# cpu-18f4455.net
KiCad netlist of a schematic drawn in EAGLE
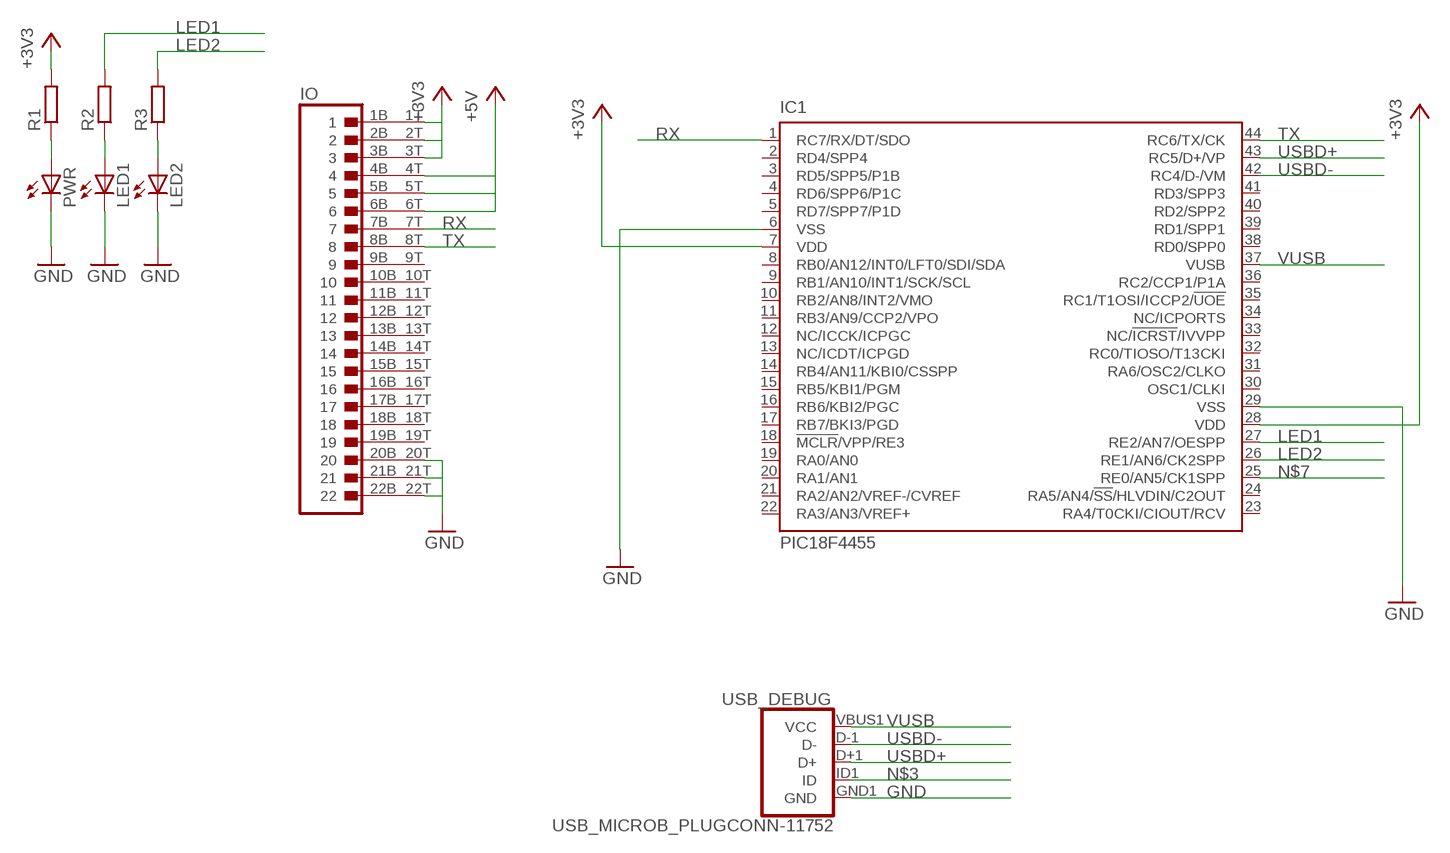
[diagram p0: schematic, sheet 1]

(export (version "E")
  (design (tool "Eeschema 10.0.6"))
  (components
    (comp (ref "IC1")
      (value "PIC18F4455")
      (footprint "eagle-import:TQFP44")
      (fields (field (name "MF") "MICROCHIP") (field (name "MPN") "PIC18F4455-I/PT"))
      (libsource (lib "eagle-import") (part "PIC18F4_TQFP455"))
    )
    (comp (ref "IO")
      (value "SIMBRD22")
      (footprint "eagle-import:SIMBRD22")
      (libsource (lib "eagle-import") (part "SIMBRD22"))
    )
    (comp (ref "LED1")
      (value "LED1206")
      (footprint "eagle-import:LED-1206")
      (libsource (lib "eagle-import") (part "LED1206"))
    )
    (comp (ref "LED2")
      (value "LED1206")
      (footprint "eagle-import:LED-1206")
      (libsource (lib "eagle-import") (part "LED1206"))
    )
    (comp (ref "PWR")
      (value "LED1206")
      (footprint "eagle-import:LED-1206")
      (libsource (lib "eagle-import") (part "LED1206"))
    )
    (comp (ref "R1")
      (value "R-EU_R0805")
      (footprint "eagle-import:R0805")
      (libsource (lib "eagle-import") (part "R-EU_R0805"))
    )
    (comp (ref "R2")
      (value "R-EU_R0805")
      (footprint "eagle-import:R0805")
      (libsource (lib "eagle-import") (part "R-EU_R0805"))
    )
    (comp (ref "R3")
      (value "R-EU_R0805")
      (footprint "eagle-import:R0805")
      (libsource (lib "eagle-import") (part "R-EU_R0805"))
    )
    (comp (ref "USB_DEBUG")
      (value "USB_MICROB_PLUGCONN-11752")
      (footprint "eagle-import:USB-B-MICRO-SMD_V03")
      (libsource (lib "eagle-import") (part "USB_MICROB_PLUGCONN-11752"))
    )
  )
  (nets
    (net (code "1") (name "+3V3") (class "Default")
      (node (ref "IC1") (pin "28") (pinfunction "VDD_28") (pintype "power_in"))
      (node (ref "IC1") (pin "7") (pinfunction "VDD_7") (pintype "power_in"))
      (node (ref "IO") (pin "1T") (pinfunction "A1_1T") (pintype "passive"))
      (node (ref "IO") (pin "2T") (pinfunction "A2_2T") (pintype "passive"))
      (node (ref "IO") (pin "3T") (pinfunction "A3_3T") (pintype "passive"))
      (node (ref "R1") (pin "2") (pinfunction "2_2") (pintype "passive"))
    )
    (net (code "2") (name "+5V") (class "Default")
      (node (ref "IO") (pin "4T") (pinfunction "A4_4T") (pintype "passive"))
      (node (ref "IO") (pin "5T") (pinfunction "A5_5T") (pintype "passive"))
      (node (ref "IO") (pin "6T") (pinfunction "A6_6T") (pintype "passive"))
    )
    (net (code "3") (name "/LED1") (class "Default")
      (node (ref "IC1") (pin "27") (pinfunction "RE2/AN7/OESPP_27") (pintype "bidirectional"))
      (node (ref "R2") (pin "2") (pinfunction "2_2") (pintype "passive"))
    )
    (net (code "4") (name "/LED2") (class "Default")
      (node (ref "IC1") (pin "26") (pinfunction "RE1/AN6/CK2SPP_26") (pintype "bidirectional"))
      (node (ref "R3") (pin "2") (pinfunction "2_2") (pintype "passive"))
    )
    (net (code "5") (name "/N$3") (class "Default")
      (node (ref "USB_DEBUG") (pin "ID1") (pinfunction "ID_ID1") (pintype "bidirectional"))
    )
    (net (code "6") (name "/N$7") (class "Default")
      (node (ref "IC1") (pin "25") (pinfunction "RE0/AN5/CK1SPP_25") (pintype "bidirectional"))
    )
    (net (code "7") (name "/RX") (class "Default")
      (node (ref "IC1") (pin "1") (pinfunction "RC7/RX/DT/SDO_1") (pintype "bidirectional"))
      (node (ref "IO") (pin "7T") (pinfunction "A7_7T") (pintype "passive"))
    )
    (net (code "8") (name "/TX") (class "Default")
      (node (ref "IC1") (pin "44") (pinfunction "RC6/TX/CK_44") (pintype "bidirectional"))
      (node (ref "IO") (pin "8T") (pinfunction "A8_8T") (pintype "passive"))
    )
    (net (code "9") (name "/USBD+") (class "Default")
      (node (ref "IC1") (pin "43") (pinfunction "RC5/D+/VP_43") (pintype "bidirectional"))
      (node (ref "USB_DEBUG") (pin "D+1") (pinfunction "D+_D+1") (pintype "bidirectional"))
    )
    (net (code "10") (name "/USBD-") (class "Default")
      (node (ref "IC1") (pin "42") (pinfunction "RC4/D-/VM_42") (pintype "bidirectional"))
      (node (ref "USB_DEBUG") (pin "D-1") (pinfunction "D-_D-1") (pintype "bidirectional"))
    )
    (net (code "11") (name "/VUSB") (class "Default")
      (node (ref "IC1") (pin "37") (pinfunction "VUSB_37") (pintype "bidirectional"))
      (node (ref "USB_DEBUG") (pin "VBUS1") (pinfunction "VCC_VBUS1") (pintype "bidirectional"))
    )
    (net (code "12") (name "GND") (class "Default")
      (node (ref "IC1") (pin "29") (pinfunction "VSS_29") (pintype "power_in"))
      (node (ref "IC1") (pin "6") (pinfunction "VSS_6") (pintype "power_in"))
      (node (ref "IO") (pin "20T") (pinfunction "A20_20T") (pintype "passive"))
      (node (ref "IO") (pin "21T") (pinfunction "A21_21T") (pintype "passive"))
      (node (ref "IO") (pin "22T") (pinfunction "A22_22T") (pintype "passive"))
      (node (ref "LED1") (pin "C") (pinfunction "C_C") (pintype "passive"))
      (node (ref "LED2") (pin "C") (pinfunction "C_C") (pintype "passive"))
      (node (ref "PWR") (pin "C") (pinfunction "C_C") (pintype "passive"))
      (node (ref "USB_DEBUG") (pin "GND1") (pinfunction "GND_GND1") (pintype "bidirectional"))
    )
    (net (code "13") (name "Net-(LED1-PadA)") (class "Default")
      (node (ref "LED1") (pin "A") (pinfunction "A_A") (pintype "passive"))
      (node (ref "R2") (pin "1") (pinfunction "1_1") (pintype "passive"))
    )
    (net (code "14") (name "Net-(LED2-PadA)") (class "Default")
      (node (ref "LED2") (pin "A") (pinfunction "A_A") (pintype "passive"))
      (node (ref "R3") (pin "1") (pinfunction "1_1") (pintype "passive"))
    )
    (net (code "15") (name "Net-(PWR-PadA)") (class "Default")
      (node (ref "PWR") (pin "A") (pinfunction "A_A") (pintype "passive"))
      (node (ref "R1") (pin "1") (pinfunction "1_1") (pintype "passive"))
    )
    (net (code "16") (name "unconnected-(IC1-NC{slash}ICCK{slash}ICPGC-Pad12)") (class "Default")
      (node (ref "IC1") (pin "12") (pinfunction "NC/ICCK/ICPGC_12") (pintype "bidirectional"))
    )
    (net (code "17") (name "unconnected-(IC1-NC{slash}ICDT{slash}ICPGD-Pad13)") (class "Default")
      (node (ref "IC1") (pin "13") (pinfunction "NC/ICDT/ICPGD_13") (pintype "bidirectional"))
    )
    (net (code "18") (name "unconnected-(IC1-NC{slash}ICPORTS-Pad34)") (class "Default")
      (node (ref "IC1") (pin "34") (pinfunction "NC/ICPORTS_34") (pintype "input"))
    )
    (net (code "19") (name "unconnected-(IC1-NC{slash}~{ICRST}{slash}IVVPP-Pad33)") (class "Default")
      (node (ref "IC1") (pin "33") (pinfunction "NC/~{ICRST}/IVVPP_33") (pintype "input"))
    )
    (net (code "20") (name "unconnected-(IC1-OSC1{slash}CLKI-Pad30)") (class "Default")
      (node (ref "IC1") (pin "30") (pinfunction "OSC1/CLKI_30") (pintype "input"))
    )
    (net (code "21") (name "unconnected-(IC1-RA0{slash}AN0-Pad19)") (class "Default")
      (node (ref "IC1") (pin "19") (pinfunction "RA0/AN0_19") (pintype "bidirectional"))
    )
    (net (code "22") (name "unconnected-(IC1-RA1{slash}AN1-Pad20)") (class "Default")
      (node (ref "IC1") (pin "20") (pinfunction "RA1/AN1_20") (pintype "bidirectional"))
    )
    (net (code "23") (name "unconnected-(IC1-RA2{slash}AN2{slash}VREF-{slash}CVREF-Pad21)") (class "Default")
      (node (ref "IC1") (pin "21") (pinfunction "RA2/AN2/VREF-/CVREF_21") (pintype "bidirectional"))
    )
    (net (code "24") (name "unconnected-(IC1-RA3{slash}AN3{slash}VREF+-Pad22)") (class "Default")
      (node (ref "IC1") (pin "22") (pinfunction "RA3/AN3/VREF+_22") (pintype "bidirectional"))
    )
    (net (code "25") (name "unconnected-(IC1-RA4{slash}T0CKI{slash}CIOUT{slash}RCV-Pad23)") (class "Default")
      (node (ref "IC1") (pin "23") (pinfunction "RA4/T0CKI/CIOUT/RCV_23") (pintype "bidirectional"))
    )
    (net (code "26") (name "unconnected-(IC1-RA5{slash}AN4{slash}~{SS}{slash}HLVDIN{slash}C2OUT-Pad24)") (class "Default")
      (node (ref "IC1") (pin "24") (pinfunction "RA5/AN4/~{SS}/HLVDIN/C2OUT_24") (pintype "bidirectional"))
    )
    (net (code "27") (name "unconnected-(IC1-RA6{slash}OSC2{slash}CLKO-Pad31)") (class "Default")
      (node (ref "IC1") (pin "31") (pinfunction "RA6/OSC2/CLKO_31") (pintype "output"))
    )
    (net (code "28") (name "unconnected-(IC1-RB0{slash}AN12{slash}INT0{slash}LFT0{slash}SDI{slash}SDA-Pad8)") (class "Default")
      (node (ref "IC1") (pin "8") (pinfunction "RB0/AN12/INT0/LFT0/SDI/SDA_8") (pintype "bidirectional"))
    )
    (net (code "29") (name "unconnected-(IC1-RB1{slash}AN10{slash}INT1{slash}SCK{slash}SCL-Pad9)") (class "Default")
      (node (ref "IC1") (pin "9") (pinfunction "RB1/AN10/INT1/SCK/SCL_9") (pintype "bidirectional"))
    )
    (net (code "30") (name "unconnected-(IC1-RB2{slash}AN8{slash}INT2{slash}VMO-Pad10)") (class "Default")
      (node (ref "IC1") (pin "10") (pinfunction "RB2/AN8/INT2/VMO_10") (pintype "bidirectional"))
    )
    (net (code "31") (name "unconnected-(IC1-RB3{slash}AN9{slash}CCP2{slash}VPO-Pad11)") (class "Default")
      (node (ref "IC1") (pin "11") (pinfunction "RB3/AN9/CCP2/VPO_11") (pintype "bidirectional"))
    )
    (net (code "32") (name "unconnected-(IC1-RB4{slash}AN11{slash}KBI0{slash}CSSPP-Pad14)") (class "Default")
      (node (ref "IC1") (pin "14") (pinfunction "RB4/AN11/KBI0/CSSPP_14") (pintype "bidirectional"))
    )
    (net (code "33") (name "unconnected-(IC1-RB5{slash}KBI1{slash}PGM-Pad15)") (class "Default")
      (node (ref "IC1") (pin "15") (pinfunction "RB5/KBI1/PGM_15") (pintype "bidirectional"))
    )
    (net (code "34") (name "unconnected-(IC1-RB6{slash}KBI2{slash}PGC-Pad16)") (class "Default")
      (node (ref "IC1") (pin "16") (pinfunction "RB6/KBI2/PGC_16") (pintype "bidirectional"))
    )
    (net (code "35") (name "unconnected-(IC1-RB7{slash}BKI3{slash}PGD-Pad17)") (class "Default")
      (node (ref "IC1") (pin "17") (pinfunction "RB7/BKI3/PGD_17") (pintype "bidirectional"))
    )
    (net (code "36") (name "unconnected-(IC1-RC0{slash}TIOSO{slash}T13CKI-Pad32)") (class "Default")
      (node (ref "IC1") (pin "32") (pinfunction "RC0/TIOSO/T13CKI_32") (pintype "bidirectional"))
    )
    (net (code "37") (name "unconnected-(IC1-RC1{slash}T1OSI{slash}ICCP2{slash}~{UOE}-Pad35)") (class "Default")
      (node (ref "IC1") (pin "35") (pinfunction "RC1/T1OSI/ICCP2/~{UOE}_35") (pintype "bidirectional"))
    )
    (net (code "38") (name "unconnected-(IC1-RC2{slash}CCP1{slash}P1A-Pad36)") (class "Default")
      (node (ref "IC1") (pin "36") (pinfunction "RC2/CCP1/P1A_36") (pintype "bidirectional"))
    )
    (net (code "39") (name "unconnected-(IC1-RD0{slash}SPP0-Pad38)") (class "Default")
      (node (ref "IC1") (pin "38") (pinfunction "RD0/SPP0_38") (pintype "bidirectional"))
    )
    (net (code "40") (name "unconnected-(IC1-RD1{slash}SPP1-Pad39)") (class "Default")
      (node (ref "IC1") (pin "39") (pinfunction "RD1/SPP1_39") (pintype "bidirectional"))
    )
    (net (code "41") (name "unconnected-(IC1-RD2{slash}SPP2-Pad40)") (class "Default")
      (node (ref "IC1") (pin "40") (pinfunction "RD2/SPP2_40") (pintype "bidirectional"))
    )
    (net (code "42") (name "unconnected-(IC1-RD3{slash}SPP3-Pad41)") (class "Default")
      (node (ref "IC1") (pin "41") (pinfunction "RD3/SPP3_41") (pintype "bidirectional"))
    )
    (net (code "43") (name "unconnected-(IC1-RD4{slash}SPP4-Pad2)") (class "Default")
      (node (ref "IC1") (pin "2") (pinfunction "RD4/SPP4_2") (pintype "bidirectional"))
    )
    (net (code "44") (name "unconnected-(IC1-RD5{slash}SPP5{slash}P1B-Pad3)") (class "Default")
      (node (ref "IC1") (pin "3") (pinfunction "RD5/SPP5/P1B_3") (pintype "bidirectional"))
    )
    (net (code "45") (name "unconnected-(IC1-RD6{slash}SPP6{slash}P1C-Pad4)") (class "Default")
      (node (ref "IC1") (pin "4") (pinfunction "RD6/SPP6/P1C_4") (pintype "bidirectional"))
    )
    (net (code "46") (name "unconnected-(IC1-RD7{slash}SPP7{slash}P1D-Pad5)") (class "Default")
      (node (ref "IC1") (pin "5") (pinfunction "RD7/SPP7/P1D_5") (pintype "bidirectional"))
    )
    (net (code "47") (name "unconnected-(IC1-~{MCLR}{slash}VPP{slash}RE3-Pad18)") (class "Default")
      (node (ref "IC1") (pin "18") (pinfunction "~{MCLR}/VPP/RE3_18") (pintype "input"))
    )
    (net (code "48") (name "unconnected-(IO-1-Pad1B)") (class "Default")
      (node (ref "IO") (pin "1B") (pinfunction "1_1B") (pintype "passive"))
    )
    (net (code "49") (name "unconnected-(IO-2-Pad2B)") (class "Default")
      (node (ref "IO") (pin "2B") (pinfunction "2_2B") (pintype "passive"))
    )
    (net (code "50") (name "unconnected-(IO-3-Pad3B)") (class "Default")
      (node (ref "IO") (pin "3B") (pinfunction "3_3B") (pintype "passive"))
    )
    (net (code "51") (name "unconnected-(IO-4-Pad4B)") (class "Default")
      (node (ref "IO") (pin "4B") (pinfunction "4_4B") (pintype "passive"))
    )
    (net (code "52") (name "unconnected-(IO-5-Pad5B)") (class "Default")
      (node (ref "IO") (pin "5B") (pinfunction "5_5B") (pintype "passive"))
    )
    (net (code "53") (name "unconnected-(IO-6-Pad6B)") (class "Default")
      (node (ref "IO") (pin "6B") (pinfunction "6_6B") (pintype "passive"))
    )
    (net (code "54") (name "unconnected-(IO-7-Pad7B)") (class "Default")
      (node (ref "IO") (pin "7B") (pinfunction "7_7B") (pintype "passive"))
    )
    (net (code "55") (name "unconnected-(IO-8-Pad8B)") (class "Default")
      (node (ref "IO") (pin "8B") (pinfunction "8_8B") (pintype "passive"))
    )
    (net (code "56") (name "unconnected-(IO-9-Pad9B)") (class "Default")
      (node (ref "IO") (pin "9B") (pinfunction "9_9B") (pintype "passive"))
    )
    (net (code "57") (name "unconnected-(IO-10-Pad10B)") (class "Default")
      (node (ref "IO") (pin "10B") (pinfunction "10_10B") (pintype "passive"))
    )
    (net (code "58") (name "unconnected-(IO-11-Pad11B)") (class "Default")
      (node (ref "IO") (pin "11B") (pinfunction "11_11B") (pintype "passive"))
    )
    (net (code "59") (name "unconnected-(IO-12-Pad12B)") (class "Default")
      (node (ref "IO") (pin "12B") (pinfunction "12_12B") (pintype "passive"))
    )
    (net (code "60") (name "unconnected-(IO-13-Pad13B)") (class "Default")
      (node (ref "IO") (pin "13B") (pinfunction "13_13B") (pintype "passive"))
    )
    (net (code "61") (name "unconnected-(IO-14-Pad14B)") (class "Default")
      (node (ref "IO") (pin "14B") (pinfunction "14_14B") (pintype "passive"))
    )
    (net (code "62") (name "unconnected-(IO-15-Pad15B)") (class "Default")
      (node (ref "IO") (pin "15B") (pinfunction "15_15B") (pintype "passive"))
    )
    (net (code "63") (name "unconnected-(IO-16-Pad16B)") (class "Default")
      (node (ref "IO") (pin "16B") (pinfunction "16_16B") (pintype "passive"))
    )
    (net (code "64") (name "unconnected-(IO-17-Pad17B)") (class "Default")
      (node (ref "IO") (pin "17B") (pinfunction "17_17B") (pintype "passive"))
    )
    (net (code "65") (name "unconnected-(IO-18-Pad18B)") (class "Default")
      (node (ref "IO") (pin "18B") (pinfunction "18_18B") (pintype "passive"))
    )
    (net (code "66") (name "unconnected-(IO-19-Pad19B)") (class "Default")
      (node (ref "IO") (pin "19B") (pinfunction "19_19B") (pintype "passive"))
    )
    (net (code "67") (name "unconnected-(IO-20-Pad20B)") (class "Default")
      (node (ref "IO") (pin "20B") (pinfunction "20_20B") (pintype "passive"))
    )
    (net (code "68") (name "unconnected-(IO-21-Pad21B)") (class "Default")
      (node (ref "IO") (pin "21B") (pinfunction "21_21B") (pintype "passive"))
    )
    (net (code "69") (name "unconnected-(IO-22-Pad22B)") (class "Default")
      (node (ref "IO") (pin "22B") (pinfunction "22_22B") (pintype "passive"))
    )
    (net (code "70") (name "unconnected-(IO-A9-Pad9T)") (class "Default")
      (node (ref "IO") (pin "9T") (pinfunction "A9_9T") (pintype "passive"))
    )
    (net (code "71") (name "unconnected-(IO-A10-Pad10T)") (class "Default")
      (node (ref "IO") (pin "10T") (pinfunction "A10_10T") (pintype "passive"))
    )
    (net (code "72") (name "unconnected-(IO-A11-Pad11T)") (class "Default")
      (node (ref "IO") (pin "11T") (pinfunction "A11_11T") (pintype "passive"))
    )
    (net (code "73") (name "unconnected-(IO-A12-Pad12T)") (class "Default")
      (node (ref "IO") (pin "12T") (pinfunction "A12_12T") (pintype "passive"))
    )
    (net (code "74") (name "unconnected-(IO-A13-Pad13T)") (class "Default")
      (node (ref "IO") (pin "13T") (pinfunction "A13_13T") (pintype "passive"))
    )
    (net (code "75") (name "unconnected-(IO-A14-Pad14T)") (class "Default")
      (node (ref "IO") (pin "14T") (pinfunction "A14_14T") (pintype "passive"))
    )
    (net (code "76") (name "unconnected-(IO-A15-Pad15T)") (class "Default")
      (node (ref "IO") (pin "15T") (pinfunction "A15_15T") (pintype "passive"))
    )
    (net (code "77") (name "unconnected-(IO-A16-Pad16T)") (class "Default")
      (node (ref "IO") (pin "16T") (pinfunction "A16_16T") (pintype "passive"))
    )
    (net (code "78") (name "unconnected-(IO-A17-Pad17T)") (class "Default")
      (node (ref "IO") (pin "17T") (pinfunction "A17_17T") (pintype "passive"))
    )
    (net (code "79") (name "unconnected-(IO-A18-Pad18T)") (class "Default")
      (node (ref "IO") (pin "18T") (pinfunction "A18_18T") (pintype "passive"))
    )
    (net (code "80") (name "unconnected-(IO-A19-Pad19T)") (class "Default")
      (node (ref "IO") (pin "19T") (pinfunction "A19_19T") (pintype "passive"))
    )
  )
)
